# 2023-06-29_LVMi_Thermistors.net
KiCad netlist of a schematic drawn in EAGLE
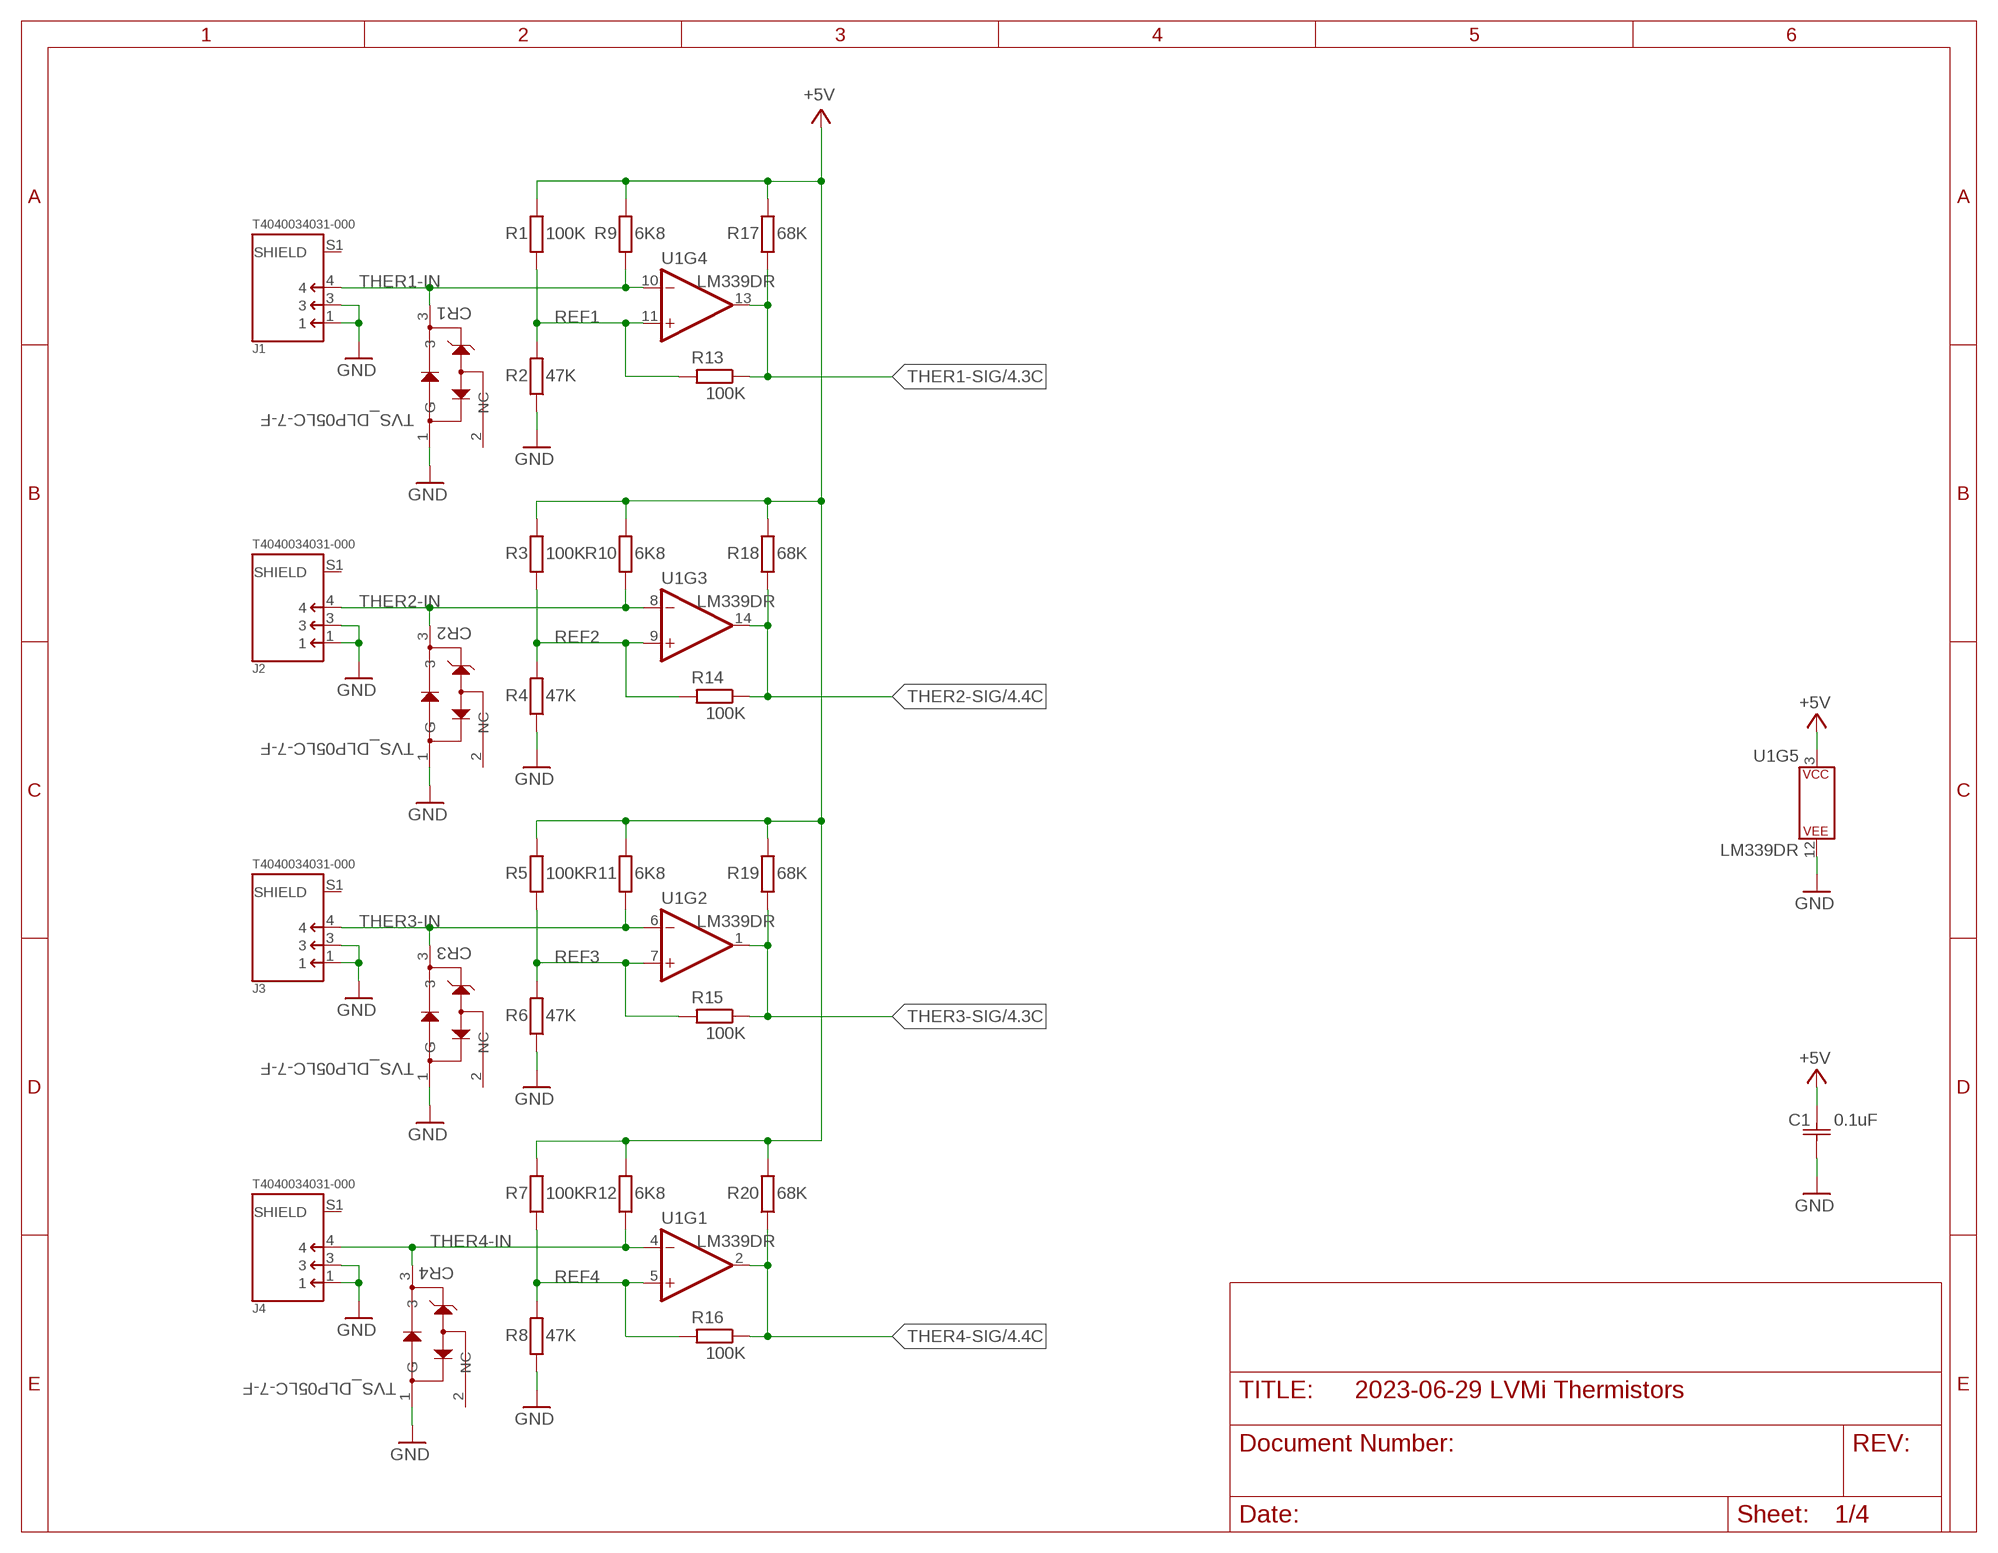
[diagram p0: schematic, sheet 1]
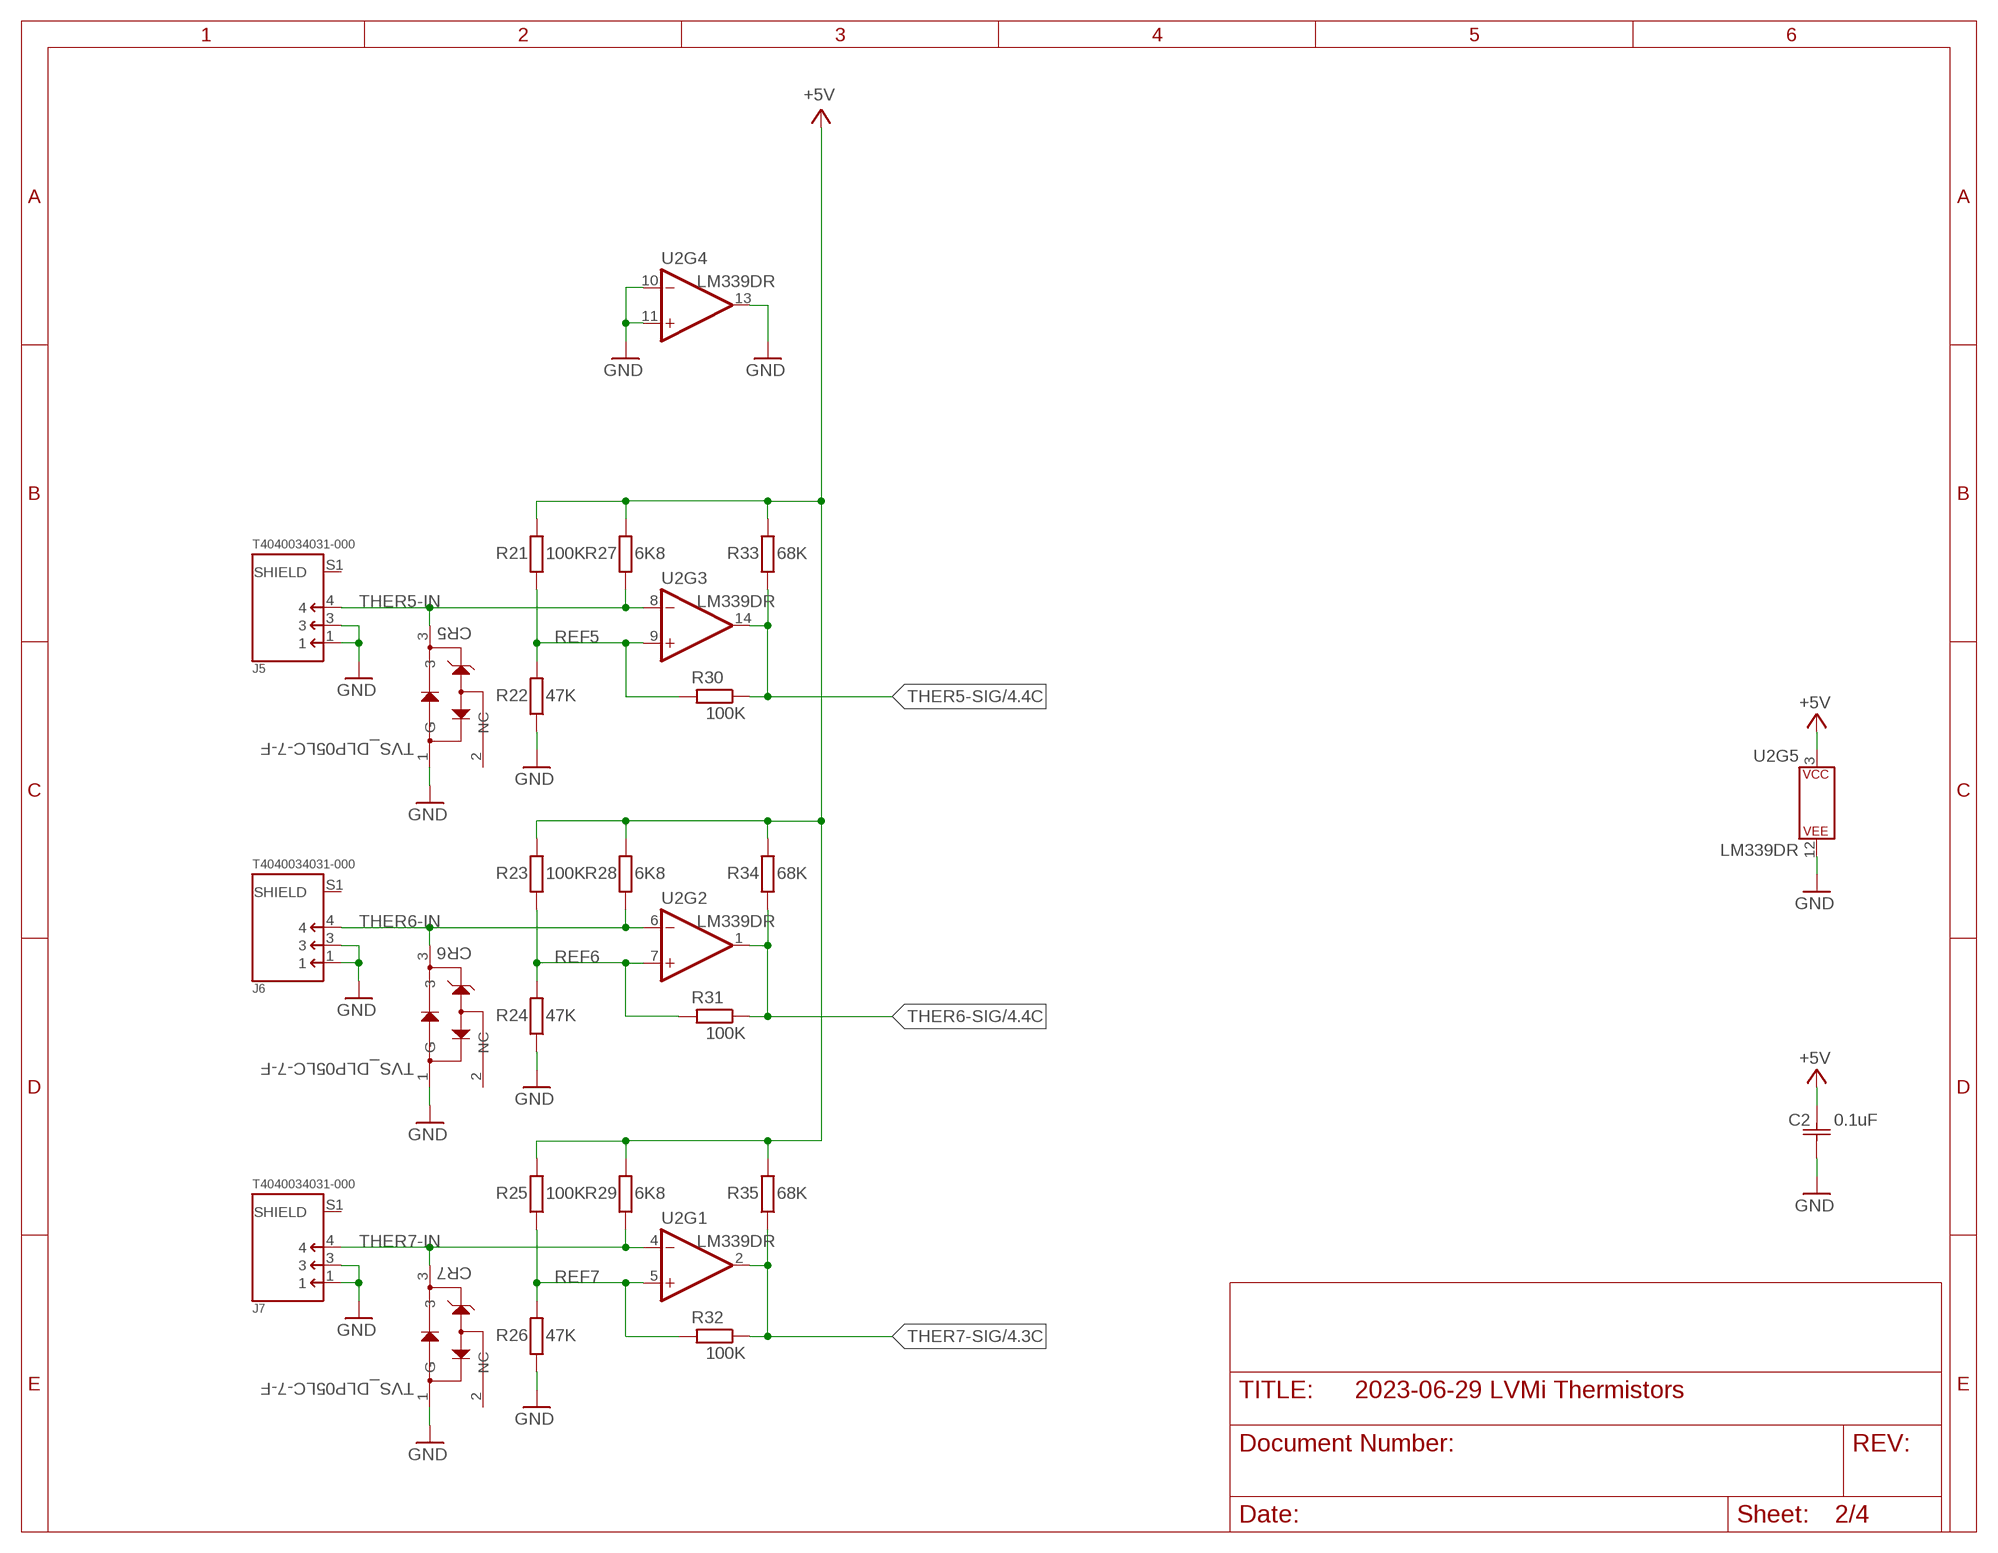
[diagram p1: schematic, sheet 2]
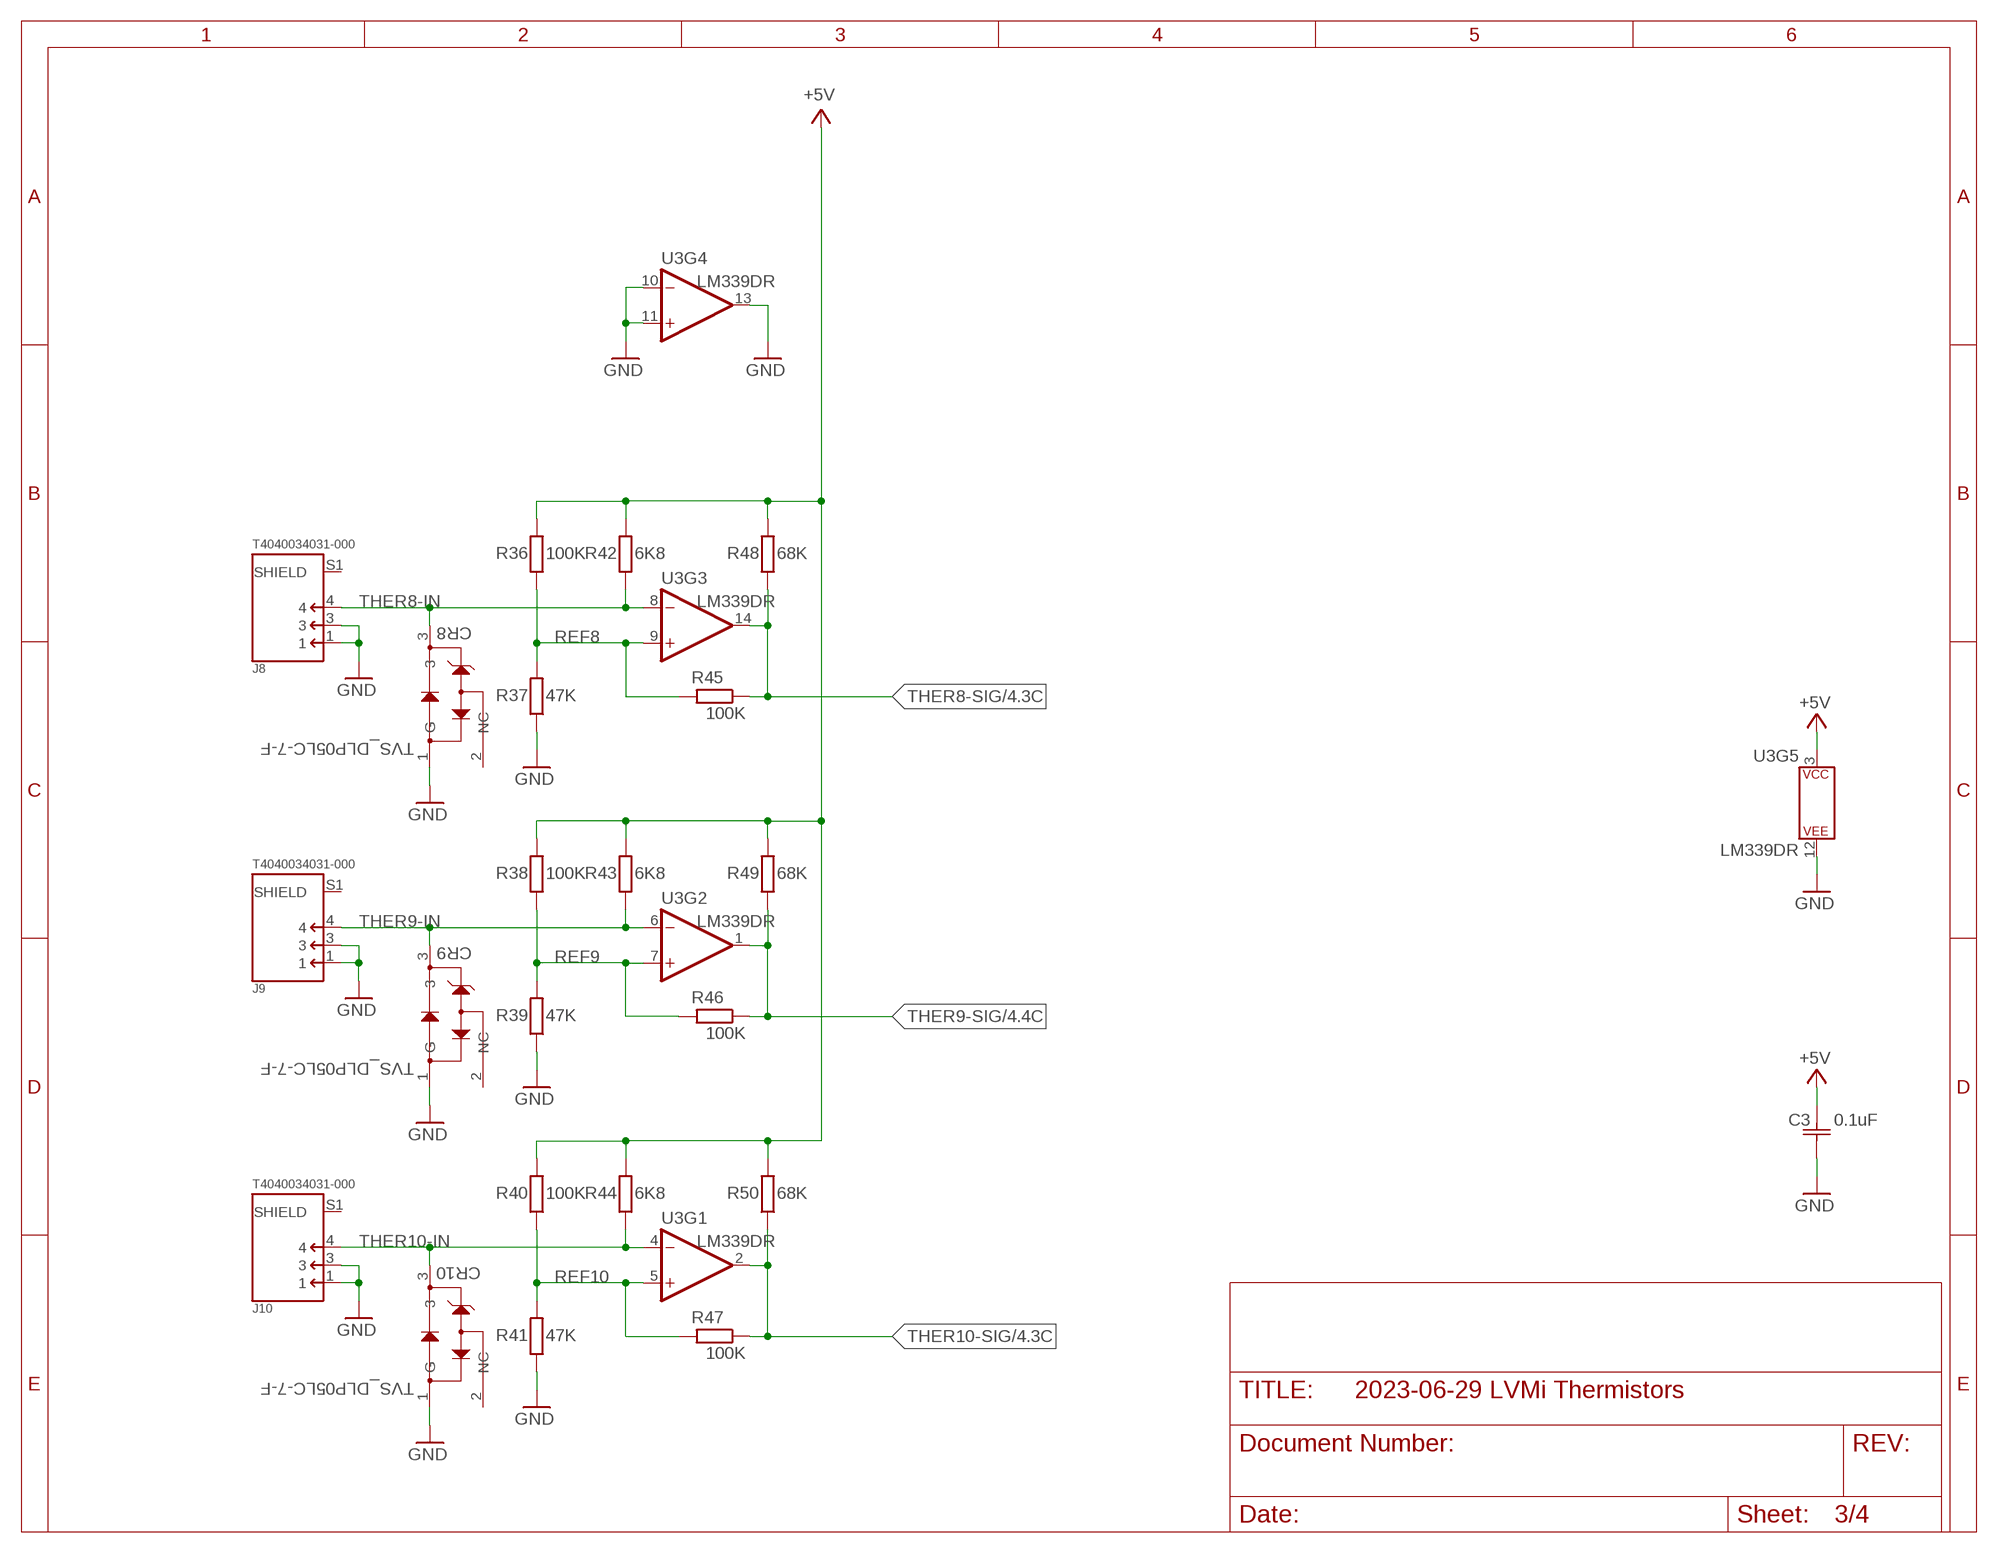
[diagram p2: schematic, sheet 3]
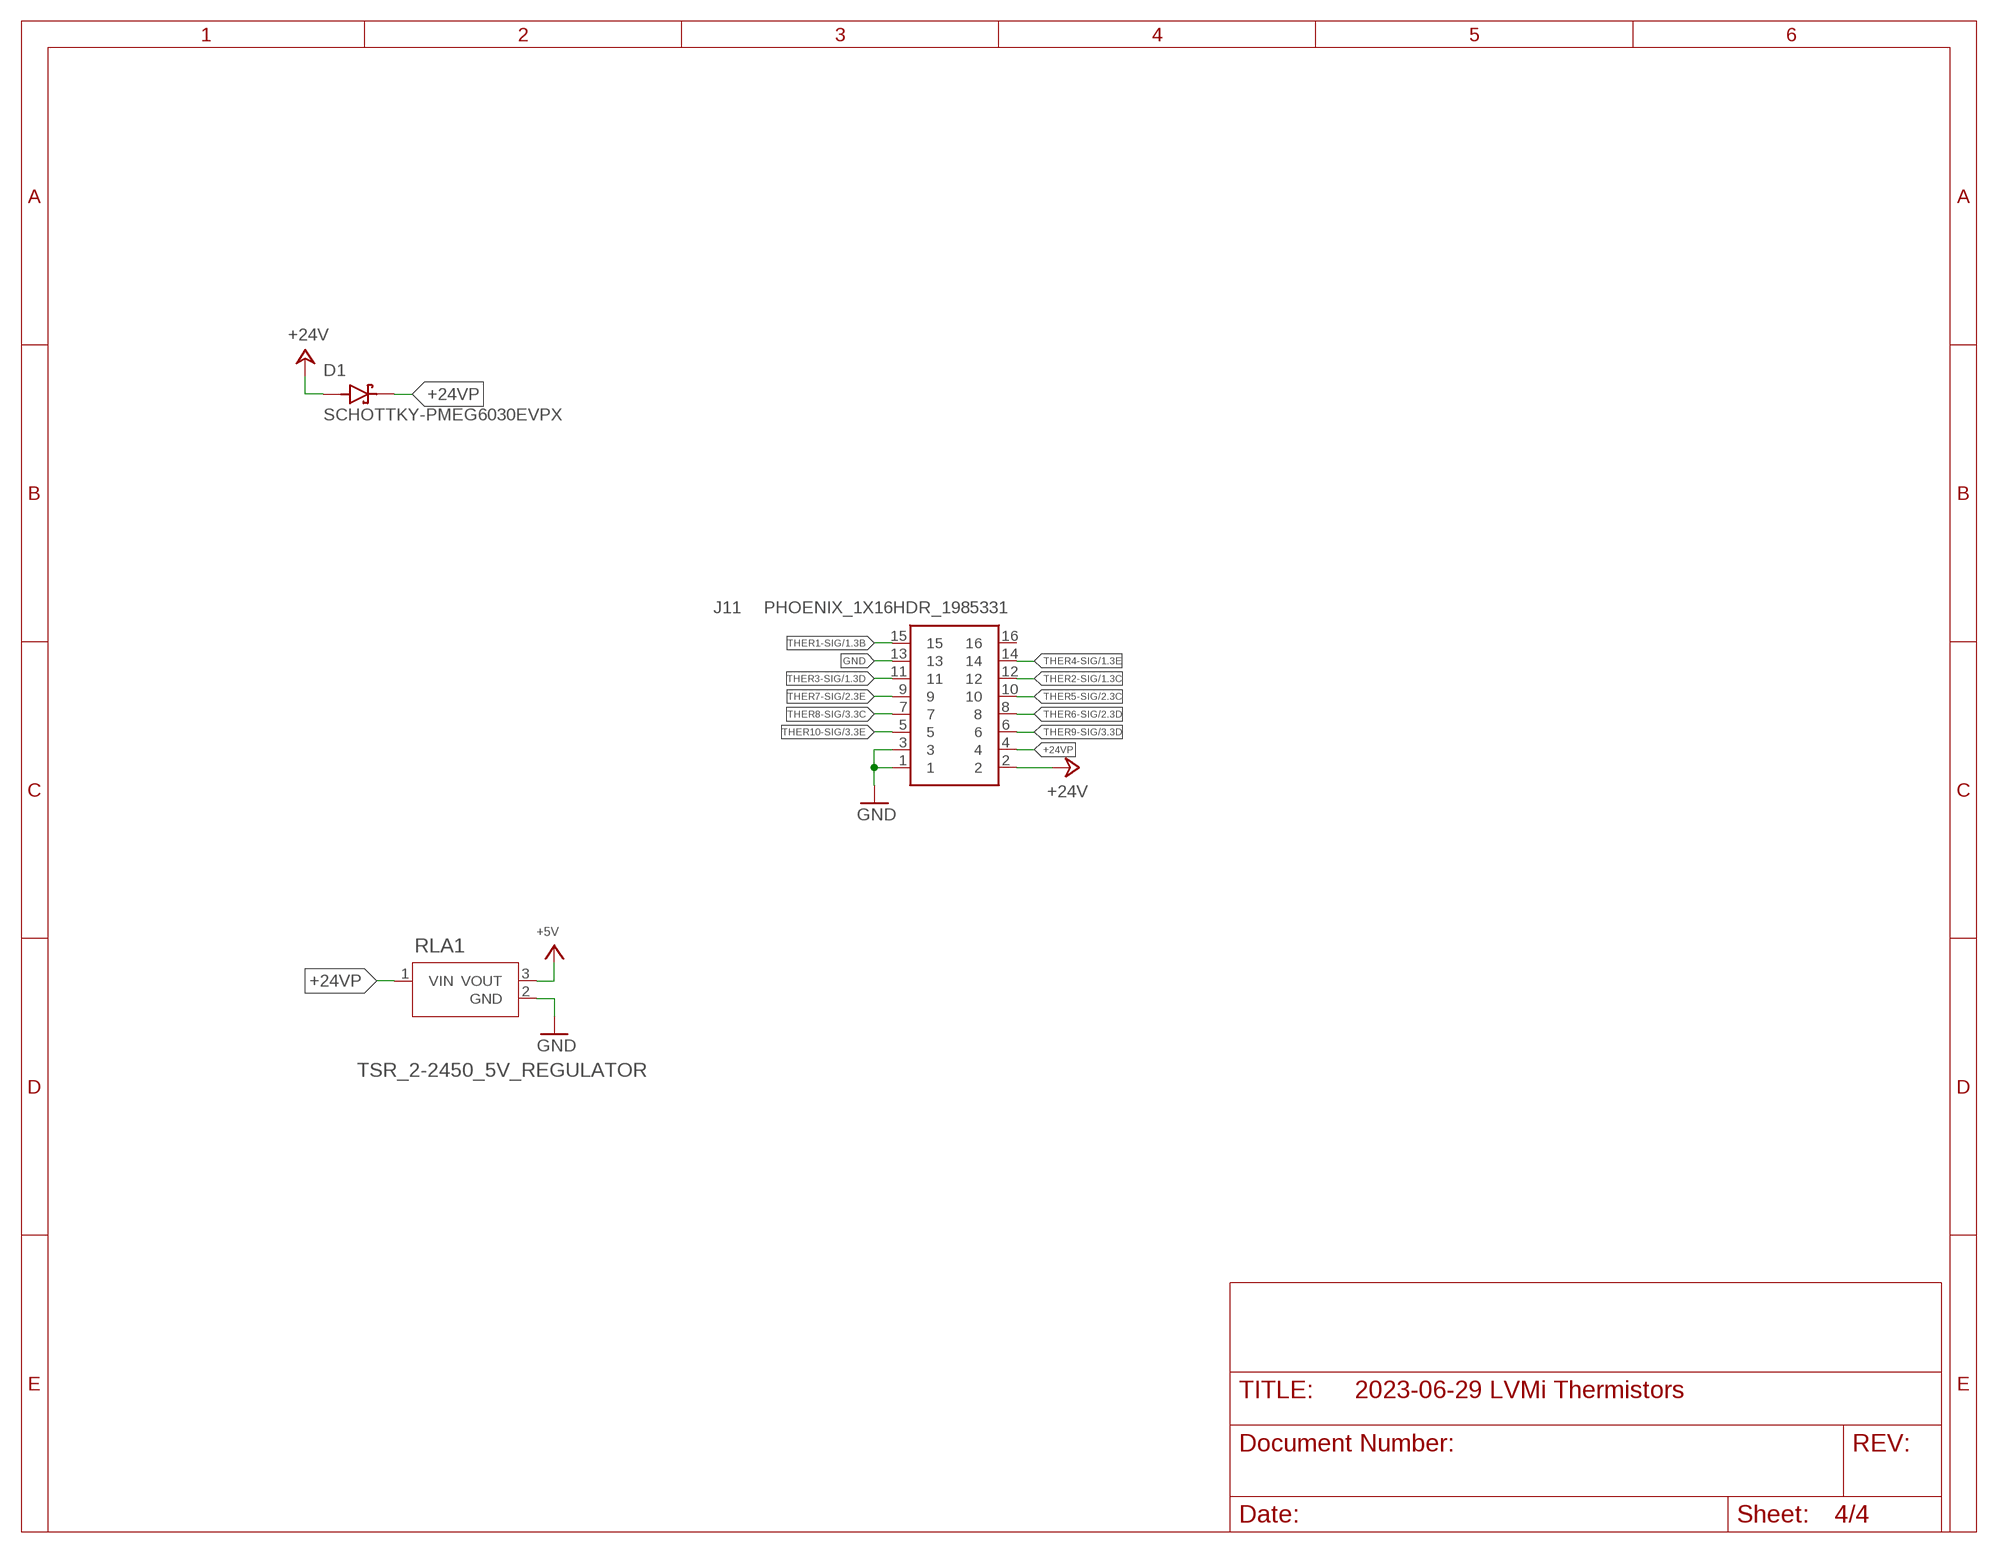
[diagram p3: schematic, sheet 4]

(export (version "E")
  (design (tool "Eeschema 10.0.6"))
  (components
    (comp (ref "D1")
      (value "SCHOTTKY-PMEG6030EVPX")
      (footprint "eagle-import:DIO_PMEG6030EVPX")
      (fields
        (field (name "DIGI-KEY_PART_NUMBER") "1727-1349-1-ND")
        (field (name "MF") "Nexperia USA")
        (field (name "MP") "PMEG6030EVPX")
      )
      (libsource (lib "eagle-import") (part "SCHOTTKY-PMEG6030EVPX"))
    )
    (comp (ref "J11")
      (value "PHOENIX_1X16HDR_1985331")
      (footprint "eagle-import:1985331")
      (fields
        (field (name "MANUFACTURER_PART_NUMBER") "1985331")
        (field (name "MOUSER_PART_NUMBER") "651-1985331")
      )
      (libsource (lib "eagle-import") (part "PHOENIX_1X16HDR_1985331"))
    )
    (comp (ref "RLA1")
      (value "TSR_2-2450_5V_REGULATOR")
      (footprint "eagle-import:TSR2-SINGLE_TRP")
      (fields
        (field (name "MANUFACTURER_PART_NUMBER") "TSR 2-2450")
        (field (name "COPYRIGHT") "Copyright (C) 2022 Ultra Librarian. All rights reserved.")
      )
      (libsource (lib "eagle-import") (part "TSR_2-2450_5V_REGULATOR"))
    )
    (comp (ref "C2")
      (value "0.1uF")
      (footprint "eagle-import:K104K15X7RF5TL2_VIS")
      (fields
        (field (name "MANUFACTURER_PART_NUMBER") "K104K15X7RF5TL2")
        (field (name "COPYRIGHT") "Copyright (C) 2023 Ultra Librarian. All rights reserved.")
      )
      (libsource (lib "eagle-import") (part "CAPTHRUHOLE"))
    )
    (comp (ref "CR5")
      (value "TVS_DLP05LC-7-F")
      (footprint "eagle-import:SOT23_DLP05LC_DIO")
      (fields
        (field (name "MANUFACTURER_PART_NUMBER") "DLP05LC-7-F")
        (field (name "COPYRIGHT") "Copyright (C) 2023 Ultra Librarian. All rights reserved.")
      )
      (libsource (lib "eagle-import") (part "TVS_DLP05LC-7-F"))
    )
    (comp (ref "CR6")
      (value "TVS_DLP05LC-7-F")
      (footprint "eagle-import:SOT23_DLP05LC_DIO")
      (fields
        (field (name "MANUFACTURER_PART_NUMBER") "DLP05LC-7-F")
        (field (name "COPYRIGHT") "Copyright (C) 2023 Ultra Librarian. All rights reserved.")
      )
      (libsource (lib "eagle-import") (part "TVS_DLP05LC-7-F"))
    )
    (comp (ref "CR7")
      (value "TVS_DLP05LC-7-F")
      (footprint "eagle-import:SOT23_DLP05LC_DIO")
      (fields
        (field (name "MANUFACTURER_PART_NUMBER") "DLP05LC-7-F")
        (field (name "COPYRIGHT") "Copyright (C) 2023 Ultra Librarian. All rights reserved.")
      )
      (libsource (lib "eagle-import") (part "TVS_DLP05LC-7-F"))
    )
    (comp (ref "J5")
      (value "T4040034031-000")
      (footprint "eagle-import:TE_T4040034031-000")
      (fields (field (name "MANUFACTURER") "TE "))
      (libsource (lib "eagle-import") (part "T4040034031-000"))
    )
    (comp (ref "J6")
      (value "T4040034031-000")
      (footprint "eagle-import:TE_T4040034031-000")
      (fields (field (name "MANUFACTURER") "TE "))
      (libsource (lib "eagle-import") (part "T4040034031-000"))
    )
    (comp (ref "J7")
      (value "T4040034031-000")
      (footprint "eagle-import:TE_T4040034031-000")
      (fields (field (name "MANUFACTURER") "TE "))
      (libsource (lib "eagle-import") (part "T4040034031-000"))
    )
    (comp (ref "R21")
      (value "100K")
      (footprint "eagle-import:0207_10")
      (libsource (lib "eagle-import") (part "R-EU_0207/10"))
    )
    (comp (ref "R22")
      (value "47K")
      (footprint "eagle-import:0207_10")
      (libsource (lib "eagle-import") (part "R-EU_0207/10"))
    )
    (comp (ref "R23")
      (value "100K")
      (footprint "eagle-import:0207_10")
      (libsource (lib "eagle-import") (part "R-EU_0207/10"))
    )
    (comp (ref "R24")
      (value "47K")
      (footprint "eagle-import:0207_10")
      (libsource (lib "eagle-import") (part "R-EU_0207/10"))
    )
    (comp (ref "R25")
      (value "100K")
      (footprint "eagle-import:0207_10")
      (libsource (lib "eagle-import") (part "R-EU_0207/10"))
    )
    (comp (ref "R26")
      (value "47K")
      (footprint "eagle-import:0207_10")
      (libsource (lib "eagle-import") (part "R-EU_0207/10"))
    )
    (comp (ref "R27")
      (value "6K8")
      (footprint "eagle-import:0207_10")
      (libsource (lib "eagle-import") (part "R-EU_0207/10"))
    )
    (comp (ref "R28")
      (value "6K8")
      (footprint "eagle-import:0207_10")
      (libsource (lib "eagle-import") (part "R-EU_0207/10"))
    )
    (comp (ref "R29")
      (value "6K8")
      (footprint "eagle-import:0207_10")
      (libsource (lib "eagle-import") (part "R-EU_0207/10"))
    )
    (comp (ref "R30")
      (value "100K")
      (footprint "eagle-import:0207_10")
      (libsource (lib "eagle-import") (part "R-EU_0207/10"))
    )
    (comp (ref "R31")
      (value "100K")
      (footprint "eagle-import:0207_10")
      (libsource (lib "eagle-import") (part "R-EU_0207/10"))
    )
    (comp (ref "R32")
      (value "100K")
      (footprint "eagle-import:0207_10")
      (libsource (lib "eagle-import") (part "R-EU_0207/10"))
    )
    (comp (ref "R33")
      (value "68K")
      (footprint "eagle-import:0207_10")
      (libsource (lib "eagle-import") (part "R-EU_0207/10"))
    )
    (comp (ref "R34")
      (value "68K")
      (footprint "eagle-import:0207_10")
      (libsource (lib "eagle-import") (part "R-EU_0207/10"))
    )
    (comp (ref "R35")
      (value "68K")
      (footprint "eagle-import:0207_10")
      (libsource (lib "eagle-import") (part "R-EU_0207/10"))
    )
    (comp (ref "U2")
      (value "LM339DR")
      (footprint "eagle-import:SOIC127P599X175-14")
      (libsource (lib "eagle-import") (part "LM339SOIC-14"))
    )
    (comp (ref "C3")
      (value "0.1uF")
      (footprint "eagle-import:K104K15X7RF5TL2_VIS")
      (fields
        (field (name "MANUFACTURER_PART_NUMBER") "K104K15X7RF5TL2")
        (field (name "COPYRIGHT") "Copyright (C) 2023 Ultra Librarian. All rights reserved.")
      )
      (libsource (lib "eagle-import") (part "CAPTHRUHOLE"))
    )
    (comp (ref "CR8")
      (value "TVS_DLP05LC-7-F")
      (footprint "eagle-import:SOT23_DLP05LC_DIO")
      (fields
        (field (name "MANUFACTURER_PART_NUMBER") "DLP05LC-7-F")
        (field (name "COPYRIGHT") "Copyright (C) 2023 Ultra Librarian. All rights reserved.")
      )
      (libsource (lib "eagle-import") (part "TVS_DLP05LC-7-F"))
    )
    (comp (ref "CR9")
      (value "TVS_DLP05LC-7-F")
      (footprint "eagle-import:SOT23_DLP05LC_DIO")
      (fields
        (field (name "MANUFACTURER_PART_NUMBER") "DLP05LC-7-F")
        (field (name "COPYRIGHT") "Copyright (C) 2023 Ultra Librarian. All rights reserved.")
      )
      (libsource (lib "eagle-import") (part "TVS_DLP05LC-7-F"))
    )
    (comp (ref "CR10")
      (value "TVS_DLP05LC-7-F")
      (footprint "eagle-import:SOT23_DLP05LC_DIO")
      (fields
        (field (name "MANUFACTURER_PART_NUMBER") "DLP05LC-7-F")
        (field (name "COPYRIGHT") "Copyright (C) 2023 Ultra Librarian. All rights reserved.")
      )
      (libsource (lib "eagle-import") (part "TVS_DLP05LC-7-F"))
    )
    (comp (ref "J8")
      (value "T4040034031-000")
      (footprint "eagle-import:TE_T4040034031-000")
      (fields (field (name "MANUFACTURER") "TE "))
      (libsource (lib "eagle-import") (part "T4040034031-000"))
    )
    (comp (ref "J9")
      (value "T4040034031-000")
      (footprint "eagle-import:TE_T4040034031-000")
      (fields (field (name "MANUFACTURER") "TE "))
      (libsource (lib "eagle-import") (part "T4040034031-000"))
    )
    (comp (ref "J10")
      (value "T4040034031-000")
      (footprint "eagle-import:TE_T4040034031-000")
      (fields (field (name "MANUFACTURER") "TE "))
      (libsource (lib "eagle-import") (part "T4040034031-000"))
    )
    (comp (ref "R36")
      (value "100K")
      (footprint "eagle-import:0207_10")
      (libsource (lib "eagle-import") (part "R-EU_0207/10"))
    )
    (comp (ref "R37")
      (value "47K")
      (footprint "eagle-import:0207_10")
      (libsource (lib "eagle-import") (part "R-EU_0207/10"))
    )
    (comp (ref "R38")
      (value "100K")
      (footprint "eagle-import:0207_10")
      (libsource (lib "eagle-import") (part "R-EU_0207/10"))
    )
    (comp (ref "R39")
      (value "47K")
      (footprint "eagle-import:0207_10")
      (libsource (lib "eagle-import") (part "R-EU_0207/10"))
    )
    (comp (ref "R40")
      (value "100K")
      (footprint "eagle-import:0207_10")
      (libsource (lib "eagle-import") (part "R-EU_0207/10"))
    )
    (comp (ref "R41")
      (value "47K")
      (footprint "eagle-import:0207_10")
      (libsource (lib "eagle-import") (part "R-EU_0207/10"))
    )
    (comp (ref "R42")
      (value "6K8")
      (footprint "eagle-import:0207_10")
      (libsource (lib "eagle-import") (part "R-EU_0207/10"))
    )
    (comp (ref "R43")
      (value "6K8")
      (footprint "eagle-import:0207_10")
      (libsource (lib "eagle-import") (part "R-EU_0207/10"))
    )
    (comp (ref "R44")
      (value "6K8")
      (footprint "eagle-import:0207_10")
      (libsource (lib "eagle-import") (part "R-EU_0207/10"))
    )
    (comp (ref "R45")
      (value "100K")
      (footprint "eagle-import:0207_10")
      (libsource (lib "eagle-import") (part "R-EU_0207/10"))
    )
    (comp (ref "R46")
      (value "100K")
      (footprint "eagle-import:0207_10")
      (libsource (lib "eagle-import") (part "R-EU_0207/10"))
    )
    (comp (ref "R47")
      (value "100K")
      (footprint "eagle-import:0207_10")
      (libsource (lib "eagle-import") (part "R-EU_0207/10"))
    )
    (comp (ref "R48")
      (value "68K")
      (footprint "eagle-import:0207_10")
      (libsource (lib "eagle-import") (part "R-EU_0207/10"))
    )
    (comp (ref "R49")
      (value "68K")
      (footprint "eagle-import:0207_10")
      (libsource (lib "eagle-import") (part "R-EU_0207/10"))
    )
    (comp (ref "R50")
      (value "68K")
      (footprint "eagle-import:0207_10")
      (libsource (lib "eagle-import") (part "R-EU_0207/10"))
    )
    (comp (ref "U3")
      (value "LM339DR")
      (footprint "eagle-import:SOIC127P599X175-14")
      (libsource (lib "eagle-import") (part "LM339SOIC-14"))
    )
    (comp (ref "C1")
      (value "0.1uF")
      (footprint "eagle-import:K104K15X7RF5TL2_VIS")
      (fields
        (field (name "MANUFACTURER_PART_NUMBER") "K104K15X7RF5TL2")
        (field (name "COPYRIGHT") "Copyright (C) 2023 Ultra Librarian. All rights reserved.")
      )
      (libsource (lib "eagle-import") (part "CAPTHRUHOLE"))
    )
    (comp (ref "CR1")
      (value "TVS_DLP05LC-7-F")
      (footprint "eagle-import:SOT23_DLP05LC_DIO")
      (fields
        (field (name "MANUFACTURER_PART_NUMBER") "DLP05LC-7-F")
        (field (name "COPYRIGHT") "Copyright (C) 2023 Ultra Librarian. All rights reserved.")
      )
      (libsource (lib "eagle-import") (part "TVS_DLP05LC-7-F"))
    )
    (comp (ref "CR2")
      (value "TVS_DLP05LC-7-F")
      (footprint "eagle-import:SOT23_DLP05LC_DIO")
      (fields
        (field (name "MANUFACTURER_PART_NUMBER") "DLP05LC-7-F")
        (field (name "COPYRIGHT") "Copyright (C) 2023 Ultra Librarian. All rights reserved.")
      )
      (libsource (lib "eagle-import") (part "TVS_DLP05LC-7-F"))
    )
    (comp (ref "CR3")
      (value "TVS_DLP05LC-7-F")
      (footprint "eagle-import:SOT23_DLP05LC_DIO")
      (fields
        (field (name "MANUFACTURER_PART_NUMBER") "DLP05LC-7-F")
        (field (name "COPYRIGHT") "Copyright (C) 2023 Ultra Librarian. All rights reserved.")
      )
      (libsource (lib "eagle-import") (part "TVS_DLP05LC-7-F"))
    )
    (comp (ref "CR4")
      (value "TVS_DLP05LC-7-F")
      (footprint "eagle-import:SOT23_DLP05LC_DIO")
      (fields
        (field (name "MANUFACTURER_PART_NUMBER") "DLP05LC-7-F")
        (field (name "COPYRIGHT") "Copyright (C) 2023 Ultra Librarian. All rights reserved.")
      )
      (libsource (lib "eagle-import") (part "TVS_DLP05LC-7-F"))
    )
    (comp (ref "J1")
      (value "T4040034031-000")
      (footprint "eagle-import:TE_T4040034031-000")
      (fields (field (name "MANUFACTURER") "TE "))
      (libsource (lib "eagle-import") (part "T4040034031-000"))
    )
    (comp (ref "J2")
      (value "T4040034031-000")
      (footprint "eagle-import:TE_T4040034031-000")
      (fields (field (name "MANUFACTURER") "TE "))
      (libsource (lib "eagle-import") (part "T4040034031-000"))
    )
    (comp (ref "J3")
      (value "T4040034031-000")
      (footprint "eagle-import:TE_T4040034031-000")
      (fields (field (name "MANUFACTURER") "TE "))
      (libsource (lib "eagle-import") (part "T4040034031-000"))
    )
    (comp (ref "J4")
      (value "T4040034031-000")
      (footprint "eagle-import:TE_T4040034031-000")
      (fields (field (name "MANUFACTURER") "TE "))
      (libsource (lib "eagle-import") (part "T4040034031-000"))
    )
    (comp (ref "R1")
      (value "100K")
      (footprint "eagle-import:0207_10")
      (libsource (lib "eagle-import") (part "R-EU_0207/10"))
    )
    (comp (ref "R2")
      (value "47K")
      (footprint "eagle-import:0207_10")
      (libsource (lib "eagle-import") (part "R-EU_0207/10"))
    )
    (comp (ref "R3")
      (value "100K")
      (footprint "eagle-import:0207_10")
      (libsource (lib "eagle-import") (part "R-EU_0207/10"))
    )
    (comp (ref "R4")
      (value "47K")
      (footprint "eagle-import:0207_10")
      (libsource (lib "eagle-import") (part "R-EU_0207/10"))
    )
    (comp (ref "R5")
      (value "100K")
      (footprint "eagle-import:0207_10")
      (libsource (lib "eagle-import") (part "R-EU_0207/10"))
    )
    (comp (ref "R6")
      (value "47K")
      (footprint "eagle-import:0207_10")
      (libsource (lib "eagle-import") (part "R-EU_0207/10"))
    )
    (comp (ref "R7")
      (value "100K")
      (footprint "eagle-import:0207_10")
      (libsource (lib "eagle-import") (part "R-EU_0207/10"))
    )
    (comp (ref "R8")
      (value "47K")
      (footprint "eagle-import:0207_10")
      (libsource (lib "eagle-import") (part "R-EU_0207/10"))
    )
    (comp (ref "R9")
      (value "6K8")
      (footprint "eagle-import:0207_10")
      (libsource (lib "eagle-import") (part "R-EU_0207/10"))
    )
    (comp (ref "R10")
      (value "6K8")
      (footprint "eagle-import:0207_10")
      (libsource (lib "eagle-import") (part "R-EU_0207/10"))
    )
    (comp (ref "R11")
      (value "6K8")
      (footprint "eagle-import:0207_10")
      (libsource (lib "eagle-import") (part "R-EU_0207/10"))
    )
    (comp (ref "R12")
      (value "6K8")
      (footprint "eagle-import:0207_10")
      (libsource (lib "eagle-import") (part "R-EU_0207/10"))
    )
    (comp (ref "R13")
      (value "100K")
      (footprint "eagle-import:0207_10")
      (libsource (lib "eagle-import") (part "R-EU_0207/10"))
    )
    (comp (ref "R14")
      (value "100K")
      (footprint "eagle-import:0207_10")
      (libsource (lib "eagle-import") (part "R-EU_0207/10"))
    )
    (comp (ref "R15")
      (value "100K")
      (footprint "eagle-import:0207_10")
      (libsource (lib "eagle-import") (part "R-EU_0207/10"))
    )
    (comp (ref "R16")
      (value "100K")
      (footprint "eagle-import:0207_10")
      (libsource (lib "eagle-import") (part "R-EU_0207/10"))
    )
    (comp (ref "R17")
      (value "68K")
      (footprint "eagle-import:0207_10")
      (libsource (lib "eagle-import") (part "R-EU_0207/10"))
    )
    (comp (ref "R18")
      (value "68K")
      (footprint "eagle-import:0207_10")
      (libsource (lib "eagle-import") (part "R-EU_0207/10"))
    )
    (comp (ref "R19")
      (value "68K")
      (footprint "eagle-import:0207_10")
      (libsource (lib "eagle-import") (part "R-EU_0207/10"))
    )
    (comp (ref "R20")
      (value "68K")
      (footprint "eagle-import:0207_10")
      (libsource (lib "eagle-import") (part "R-EU_0207/10"))
    )
    (comp (ref "U1")
      (value "LM339DR")
      (footprint "eagle-import:SOIC127P599X175-14")
      (libsource (lib "eagle-import") (part "LM339SOIC-14"))
    )
  )
  (nets
    (net (code "1") (name "+5V") (class "Default")
      (node (ref "C1") (pin "2") (pinfunction "2_2") (pintype "passive"))
      (node (ref "C2") (pin "2") (pinfunction "2_2") (pintype "passive"))
      (node (ref "C3") (pin "2") (pinfunction "2_2") (pintype "passive"))
      (node (ref "R1") (pin "2") (pinfunction "2_2") (pintype "passive"))
      (node (ref "R10") (pin "2") (pinfunction "2_2") (pintype "passive"))
      (node (ref "R11") (pin "2") (pinfunction "2_2") (pintype "passive"))
      (node (ref "R12") (pin "2") (pinfunction "2_2") (pintype "passive"))
      (node (ref "R17") (pin "2") (pinfunction "2_2") (pintype "passive"))
      (node (ref "R18") (pin "2") (pinfunction "2_2") (pintype "passive"))
      (node (ref "R19") (pin "2") (pinfunction "2_2") (pintype "passive"))
      (node (ref "R20") (pin "2") (pinfunction "2_2") (pintype "passive"))
      (node (ref "R21") (pin "2") (pinfunction "2_2") (pintype "passive"))
      (node (ref "R23") (pin "2") (pinfunction "2_2") (pintype "passive"))
      (node (ref "R25") (pin "2") (pinfunction "2_2") (pintype "passive"))
      (node (ref "R27") (pin "2") (pinfunction "2_2") (pintype "passive"))
      (node (ref "R28") (pin "2") (pinfunction "2_2") (pintype "passive"))
      (node (ref "R29") (pin "2") (pinfunction "2_2") (pintype "passive"))
      (node (ref "R3") (pin "2") (pinfunction "2_2") (pintype "passive"))
      (node (ref "R33") (pin "2") (pinfunction "2_2") (pintype "passive"))
      (node (ref "R34") (pin "2") (pinfunction "2_2") (pintype "passive"))
      (node (ref "R35") (pin "2") (pinfunction "2_2") (pintype "passive"))
      (node (ref "R36") (pin "2") (pinfunction "2_2") (pintype "passive"))
      (node (ref "R38") (pin "2") (pinfunction "2_2") (pintype "passive"))
      (node (ref "R40") (pin "2") (pinfunction "2_2") (pintype "passive"))
      (node (ref "R42") (pin "2") (pinfunction "2_2") (pintype "passive"))
      (node (ref "R43") (pin "2") (pinfunction "2_2") (pintype "passive"))
      (node (ref "R44") (pin "2") (pinfunction "2_2") (pintype "passive"))
      (node (ref "R48") (pin "2") (pinfunction "2_2") (pintype "passive"))
      (node (ref "R49") (pin "2") (pinfunction "2_2") (pintype "passive"))
      (node (ref "R5") (pin "2") (pinfunction "2_2") (pintype "passive"))
      (node (ref "R50") (pin "2") (pinfunction "2_2") (pintype "passive"))
      (node (ref "R7") (pin "2") (pinfunction "2_2") (pintype "passive"))
      (node (ref "R9") (pin "2") (pinfunction "2_2") (pintype "passive"))
      (node (ref "RLA1") (pin "3") (pinfunction "VOUT_3") (pintype "passive"))
      (node (ref "U1") (pin "3") (pinfunction "P$V+_3") (pintype "bidirectional"))
      (node (ref "U2") (pin "3") (pinfunction "P$V+_3") (pintype "bidirectional"))
      (node (ref "U3") (pin "3") (pinfunction "P$V+_3") (pintype "bidirectional"))
    )
    (net (code "2") (name "+24V") (class "Default")
      (node (ref "D1") (pin "2") (pinfunction "A_2") (pintype "passive"))
      (node (ref "J11") (pin "2") (pinfunction "2_2") (pintype "bidirectional"))
    )
    (net (code "3") (name "+24VP") (class "Default")
      (node (ref "D1") (pin "1") (pinfunction "K_1") (pintype "passive"))
      (node (ref "J11") (pin "4") (pinfunction "4_4") (pintype "bidirectional"))
      (node (ref "RLA1") (pin "1") (pinfunction "VIN_1") (pintype "passive"))
    )
    (net (code "4") (name "GND") (class "Default")
      (node (ref "C1") (pin "1") (pinfunction "1_1") (pintype "passive"))
      (node (ref "C2") (pin "1") (pinfunction "1_1") (pintype "passive"))
      (node (ref "C3") (pin "1") (pinfunction "1_1") (pintype "passive"))
      (node (ref "CR1") (pin "1") (pinfunction "G_1") (pintype "passive"))
      (node (ref "CR10") (pin "1") (pinfunction "G_1") (pintype "passive"))
      (node (ref "CR2") (pin "1") (pinfunction "G_1") (pintype "passive"))
      (node (ref "CR3") (pin "1") (pinfunction "G_1") (pintype "passive"))
      (node (ref "CR4") (pin "1") (pinfunction "G_1") (pintype "passive"))
      (node (ref "CR5") (pin "1") (pinfunction "G_1") (pintype "passive"))
      (node (ref "CR6") (pin "1") (pinfunction "G_1") (pintype "passive"))
      (node (ref "CR7") (pin "1") (pinfunction "G_1") (pintype "passive"))
      (node (ref "CR8") (pin "1") (pinfunction "G_1") (pintype "passive"))
      (node (ref "CR9") (pin "1") (pinfunction "G_1") (pintype "passive"))
      (node (ref "J1") (pin "1") (pinfunction "1_1") (pintype "passive"))
      (node (ref "J1") (pin "3") (pinfunction "3_3") (pintype "passive"))
      (node (ref "J10") (pin "1") (pinfunction "1_1") (pintype "passive"))
      (node (ref "J10") (pin "3") (pinfunction "3_3") (pintype "passive"))
      (node (ref "J11") (pin "1") (pinfunction "1_1") (pintype "bidirectional"))
      (node (ref "J11") (pin "13") (pinfunction "13_13") (pintype "bidirectional"))
      (node (ref "J11") (pin "3") (pinfunction "3_3") (pintype "bidirectional"))
      (node (ref "J2") (pin "1") (pinfunction "1_1") (pintype "passive"))
      (node (ref "J2") (pin "3") (pinfunction "3_3") (pintype "passive"))
      (node (ref "J3") (pin "1") (pinfunction "1_1") (pintype "passive"))
      (node (ref "J3") (pin "3") (pinfunction "3_3") (pintype "passive"))
      (node (ref "J4") (pin "1") (pinfunction "1_1") (pintype "passive"))
      (node (ref "J4") (pin "3") (pinfunction "3_3") (pintype "passive"))
      (node (ref "J5") (pin "1") (pinfunction "1_1") (pintype "passive"))
      (node (ref "J5") (pin "3") (pinfunction "3_3") (pintype "passive"))
      (node (ref "J6") (pin "1") (pinfunction "1_1") (pintype "passive"))
      (node (ref "J6") (pin "3") (pinfunction "3_3") (pintype "passive"))
      (node (ref "J7") (pin "1") (pinfunction "1_1") (pintype "passive"))
      (node (ref "J7") (pin "3") (pinfunction "3_3") (pintype "passive"))
      (node (ref "J8") (pin "1") (pinfunction "1_1") (pintype "passive"))
      (node (ref "J8") (pin "3") (pinfunction "3_3") (pintype "passive"))
      (node (ref "J9") (pin "1") (pinfunction "1_1") (pintype "passive"))
      (node (ref "J9") (pin "3") (pinfunction "3_3") (pintype "passive"))
      (node (ref "R2") (pin "1") (pinfunction "1_1") (pintype "passive"))
      (node (ref "R22") (pin "1") (pinfunction "1_1") (pintype "passive"))
      (node (ref "R24") (pin "1") (pinfunction "1_1") (pintype "passive"))
      (node (ref "R26") (pin "1") (pinfunction "1_1") (pintype "passive"))
      (node (ref "R37") (pin "1") (pinfunction "1_1") (pintype "passive"))
      (node (ref "R39") (pin "1") (pinfunction "1_1") (pintype "passive"))
      (node (ref "R4") (pin "1") (pinfunction "1_1") (pintype "passive"))
      (node (ref "R41") (pin "1") (pinfunction "1_1") (pintype "passive"))
      (node (ref "R6") (pin "1") (pinfunction "1_1") (pintype "passive"))
      (node (ref "R8") (pin "1") (pinfunction "1_1") (pintype "passive"))
      (node (ref "RLA1") (pin "2") (pinfunction "GND_2") (pintype "passive"))
      (node (ref "U1") (pin "12") (pinfunction "P$V-_12") (pintype "bidirectional"))
      (node (ref "U2") (pin "10") (pinfunction "-IN_10") (pintype "input"))
      (node (ref "U2") (pin "11") (pinfunction "+IN_11") (pintype "input"))
      (node (ref "U2") (pin "12") (pinfunction "P$V-_12") (pintype "bidirectional"))
      (node (ref "U2") (pin "13") (pinfunction "OUT_13") (pintype "output"))
      (node (ref "U3") (pin "10") (pinfunction "-IN_10") (pintype "input"))
      (node (ref "U3") (pin "11") (pinfunction "+IN_11") (pintype "input"))
      (node (ref "U3") (pin "12") (pinfunction "P$V-_12") (pintype "bidirectional"))
      (node (ref "U3") (pin "13") (pinfunction "OUT_13") (pintype "output"))
    )
    (net (code "5") (name "REF1") (class "Default")
      (node (ref "R1") (pin "1") (pinfunction "1_1") (pintype "passive"))
      (node (ref "R13") (pin "2") (pinfunction "2_2") (pintype "passive"))
      (node (ref "R2") (pin "2") (pinfunction "2_2") (pintype "passive"))
      (node (ref "U1") (pin "11") (pinfunction "+IN_11") (pintype "input"))
    )
    (net (code "6") (name "REF2") (class "Default")
      (node (ref "R14") (pin "2") (pinfunction "2_2") (pintype "passive"))
      (node (ref "R3") (pin "1") (pinfunction "1_1") (pintype "passive"))
      (node (ref "R4") (pin "2") (pinfunction "2_2") (pintype "passive"))
      (node (ref "U1") (pin "9") (pinfunction "+IN_9") (pintype "input"))
    )
    (net (code "7") (name "REF3") (class "Default")
      (node (ref "R15") (pin "2") (pinfunction "2_2") (pintype "passive"))
      (node (ref "R5") (pin "1") (pinfunction "1_1") (pintype "passive"))
      (node (ref "R6") (pin "2") (pinfunction "2_2") (pintype "passive"))
      (node (ref "U1") (pin "7") (pinfunction "+IN_7") (pintype "input"))
    )
    (net (code "8") (name "REF4") (class "Default")
      (node (ref "R16") (pin "2") (pinfunction "2_2") (pintype "passive"))
      (node (ref "R7") (pin "1") (pinfunction "1_1") (pintype "passive"))
      (node (ref "R8") (pin "2") (pinfunction "2_2") (pintype "passive"))
      (node (ref "U1") (pin "5") (pinfunction "+IN_5") (pintype "input"))
    )
    (net (code "9") (name "REF5") (class "Default")
      (node (ref "R21") (pin "1") (pinfunction "1_1") (pintype "passive"))
      (node (ref "R22") (pin "2") (pinfunction "2_2") (pintype "passive"))
      (node (ref "R30") (pin "2") (pinfunction "2_2") (pintype "passive"))
      (node (ref "U2") (pin "9") (pinfunction "+IN_9") (pintype "input"))
    )
    (net (code "10") (name "REF6") (class "Default")
      (node (ref "R23") (pin "1") (pinfunction "1_1") (pintype "passive"))
      (node (ref "R24") (pin "2") (pinfunction "2_2") (pintype "passive"))
      (node (ref "R31") (pin "2") (pinfunction "2_2") (pintype "passive"))
      (node (ref "U2") (pin "7") (pinfunction "+IN_7") (pintype "input"))
    )
    (net (code "11") (name "REF7") (class "Default")
      (node (ref "R25") (pin "1") (pinfunction "1_1") (pintype "passive"))
      (node (ref "R26") (pin "2") (pinfunction "2_2") (pintype "passive"))
      (node (ref "R32") (pin "2") (pinfunction "2_2") (pintype "passive"))
      (node (ref "U2") (pin "5") (pinfunction "+IN_5") (pintype "input"))
    )
    (net (code "12") (name "REF8") (class "Default")
      (node (ref "R36") (pin "1") (pinfunction "1_1") (pintype "passive"))
      (node (ref "R37") (pin "2") (pinfunction "2_2") (pintype "passive"))
      (node (ref "R45") (pin "2") (pinfunction "2_2") (pintype "passive"))
      (node (ref "U3") (pin "9") (pinfunction "+IN_9") (pintype "input"))
    )
    (net (code "13") (name "REF9") (class "Default")
      (node (ref "R38") (pin "1") (pinfunction "1_1") (pintype "passive"))
      (node (ref "R39") (pin "2") (pinfunction "2_2") (pintype "passive"))
      (node (ref "R46") (pin "2") (pinfunction "2_2") (pintype "passive"))
      (node (ref "U3") (pin "7") (pinfunction "+IN_7") (pintype "input"))
    )
    (net (code "14") (name "REF10") (class "Default")
      (node (ref "R40") (pin "1") (pinfunction "1_1") (pintype "passive"))
      (node (ref "R41") (pin "2") (pinfunction "2_2") (pintype "passive"))
      (node (ref "R47") (pin "2") (pinfunction "2_2") (pintype "passive"))
      (node (ref "U3") (pin "5") (pinfunction "+IN_5") (pintype "input"))
    )
    (net (code "15") (name "THER1-IN") (class "Default")
      (node (ref "CR1") (pin "3") (pinfunction "3_3") (pintype "passive"))
      (node (ref "J1") (pin "4") (pinfunction "4_4") (pintype "passive"))
      (node (ref "R9") (pin "1") (pinfunction "1_1") (pintype "passive"))
      (node (ref "U1") (pin "10") (pinfunction "-IN_10") (pintype "input"))
    )
    (net (code "16") (name "THER1-SIG") (class "Default")
      (node (ref "J11") (pin "15") (pinfunction "15_15") (pintype "bidirectional"))
      (node (ref "R13") (pin "1") (pinfunction "1_1") (pintype "passive"))
      (node (ref "R17") (pin "1") (pinfunction "1_1") (pintype "passive"))
      (node (ref "U1") (pin "13") (pinfunction "OUT_13") (pintype "output"))
    )
    (net (code "17") (name "THER2-IN") (class "Default")
      (node (ref "CR2") (pin "3") (pinfunction "3_3") (pintype "passive"))
      (node (ref "J2") (pin "4") (pinfunction "4_4") (pintype "passive"))
      (node (ref "R10") (pin "1") (pinfunction "1_1") (pintype "passive"))
      (node (ref "U1") (pin "8") (pinfunction "-IN_8") (pintype "input"))
    )
    (net (code "18") (name "THER2-SIG") (class "Default")
      (node (ref "J11") (pin "12") (pinfunction "12_12") (pintype "bidirectional"))
      (node (ref "R14") (pin "1") (pinfunction "1_1") (pintype "passive"))
      (node (ref "R18") (pin "1") (pinfunction "1_1") (pintype "passive"))
      (node (ref "U1") (pin "14") (pinfunction "OUT_14") (pintype "output"))
    )
    (net (code "19") (name "THER3-IN") (class "Default")
      (node (ref "CR3") (pin "3") (pinfunction "3_3") (pintype "passive"))
      (node (ref "J3") (pin "4") (pinfunction "4_4") (pintype "passive"))
      (node (ref "R11") (pin "1") (pinfunction "1_1") (pintype "passive"))
      (node (ref "U1") (pin "6") (pinfunction "-IN_6") (pintype "input"))
    )
    (net (code "20") (name "THER3-SIG") (class "Default")
      (node (ref "J11") (pin "11") (pinfunction "11_11") (pintype "bidirectional"))
      (node (ref "R15") (pin "1") (pinfunction "1_1") (pintype "passive"))
      (node (ref "R19") (pin "1") (pinfunction "1_1") (pintype "passive"))
      (node (ref "U1") (pin "1") (pinfunction "OUT_1") (pintype "output"))
    )
    (net (code "21") (name "THER4-IN") (class "Default")
      (node (ref "CR4") (pin "3") (pinfunction "3_3") (pintype "passive"))
      (node (ref "J4") (pin "4") (pinfunction "4_4") (pintype "passive"))
      (node (ref "R12") (pin "1") (pinfunction "1_1") (pintype "passive"))
      (node (ref "U1") (pin "4") (pinfunction "-IN_4") (pintype "input"))
    )
    (net (code "22") (name "THER4-SIG") (class "Default")
      (node (ref "J11") (pin "14") (pinfunction "14_14") (pintype "bidirectional"))
      (node (ref "R16") (pin "1") (pinfunction "1_1") (pintype "passive"))
      (node (ref "R20") (pin "1") (pinfunction "1_1") (pintype "passive"))
      (node (ref "U1") (pin "2") (pinfunction "OUT_2") (pintype "output"))
    )
    (net (code "23") (name "THER5-IN") (class "Default")
      (node (ref "CR5") (pin "3") (pinfunction "3_3") (pintype "passive"))
      (node (ref "J5") (pin "4") (pinfunction "4_4") (pintype "passive"))
      (node (ref "R27") (pin "1") (pinfunction "1_1") (pintype "passive"))
      (node (ref "U2") (pin "8") (pinfunction "-IN_8") (pintype "input"))
    )
    (net (code "24") (name "THER5-SIG") (class "Default")
      (node (ref "J11") (pin "10") (pinfunction "10_10") (pintype "bidirectional"))
      (node (ref "R30") (pin "1") (pinfunction "1_1") (pintype "passive"))
      (node (ref "R33") (pin "1") (pinfunction "1_1") (pintype "passive"))
      (node (ref "U2") (pin "14") (pinfunction "OUT_14") (pintype "output"))
    )
    (net (code "25") (name "THER6-IN") (class "Default")
      (node (ref "CR6") (pin "3") (pinfunction "3_3") (pintype "passive"))
      (node (ref "J6") (pin "4") (pinfunction "4_4") (pintype "passive"))
      (node (ref "R28") (pin "1") (pinfunction "1_1") (pintype "passive"))
      (node (ref "U2") (pin "6") (pinfunction "-IN_6") (pintype "input"))
    )
    (net (code "26") (name "THER6-SIG") (class "Default")
      (node (ref "J11") (pin "8") (pinfunction "8_8") (pintype "bidirectional"))
      (node (ref "R31") (pin "1") (pinfunction "1_1") (pintype "passive"))
      (node (ref "R34") (pin "1") (pinfunction "1_1") (pintype "passive"))
      (node (ref "U2") (pin "1") (pinfunction "OUT_1") (pintype "output"))
    )
    (net (code "27") (name "THER7-IN") (class "Default")
      (node (ref "CR7") (pin "3") (pinfunction "3_3") (pintype "passive"))
      (node (ref "J7") (pin "4") (pinfunction "4_4") (pintype "passive"))
      (node (ref "R29") (pin "1") (pinfunction "1_1") (pintype "passive"))
      (node (ref "U2") (pin "4") (pinfunction "-IN_4") (pintype "input"))
    )
    (net (code "28") (name "THER7-SIG") (class "Default")
      (node (ref "J11") (pin "9") (pinfunction "9_9") (pintype "bidirectional"))
      (node (ref "R32") (pin "1") (pinfunction "1_1") (pintype "passive"))
      (node (ref "R35") (pin "1") (pinfunction "1_1") (pintype "passive"))
      (node (ref "U2") (pin "2") (pinfunction "OUT_2") (pintype "output"))
    )
    (net (code "29") (name "THER8-IN") (class "Default")
      (node (ref "CR8") (pin "3") (pinfunction "3_3") (pintype "passive"))
      (node (ref "J8") (pin "4") (pinfunction "4_4") (pintype "passive"))
      (node (ref "R42") (pin "1") (pinfunction "1_1") (pintype "passive"))
      (node (ref "U3") (pin "8") (pinfunction "-IN_8") (pintype "input"))
    )
    (net (code "30") (name "THER8-SIG") (class "Default")
      (node (ref "J11") (pin "7") (pinfunction "7_7") (pintype "bidirectional"))
      (node (ref "R45") (pin "1") (pinfunction "1_1") (pintype "passive"))
      (node (ref "R48") (pin "1") (pinfunction "1_1") (pintype "passive"))
      (node (ref "U3") (pin "14") (pinfunction "OUT_14") (pintype "output"))
    )
    (net (code "31") (name "THER9-IN") (class "Default")
      (node (ref "CR9") (pin "3") (pinfunction "3_3") (pintype "passive"))
      (node (ref "J9") (pin "4") (pinfunction "4_4") (pintype "passive"))
      (node (ref "R43") (pin "1") (pinfunction "1_1") (pintype "passive"))
      (node (ref "U3") (pin "6") (pinfunction "-IN_6") (pintype "input"))
    )
    (net (code "32") (name "THER9-SIG") (class "Default")
      (node (ref "J11") (pin "6") (pinfunction "6_6") (pintype "bidirectional"))
      (node (ref "R46") (pin "1") (pinfunction "1_1") (pintype "passive"))
      (node (ref "R49") (pin "1") (pinfunction "1_1") (pintype "passive"))
      (node (ref "U3") (pin "1") (pinfunction "OUT_1") (pintype "output"))
    )
    (net (code "33") (name "THER10-IN") (class "Default")
      (node (ref "CR10") (pin "3") (pinfunction "3_3") (pintype "passive"))
      (node (ref "J10") (pin "4") (pinfunction "4_4") (pintype "passive"))
      (node (ref "R44") (pin "1") (pinfunction "1_1") (pintype "passive"))
      (node (ref "U3") (pin "4") (pinfunction "-IN_4") (pintype "input"))
    )
    (net (code "34") (name "THER10-SIG") (class "Default")
      (node (ref "J11") (pin "5") (pinfunction "5_5") (pintype "bidirectional"))
      (node (ref "R47") (pin "1") (pinfunction "1_1") (pintype "passive"))
      (node (ref "R50") (pin "1") (pinfunction "1_1") (pintype "passive"))
      (node (ref "U3") (pin "2") (pinfunction "OUT_2") (pintype "output"))
    )
    (net (code "35") (name "unconnected-(CR1-NC-Pad2)") (class "Default")
      (node (ref "CR1") (pin "2") (pinfunction "NC_2") (pintype "no_connect"))
    )
    (net (code "36") (name "unconnected-(CR2-NC-Pad2)") (class "Default")
      (node (ref "CR2") (pin "2") (pinfunction "NC_2") (pintype "no_connect"))
    )
    (net (code "37") (name "unconnected-(CR3-NC-Pad2)") (class "Default")
      (node (ref "CR3") (pin "2") (pinfunction "NC_2") (pintype "no_connect"))
    )
    (net (code "38") (name "unconnected-(CR4-NC-Pad2)") (class "Default")
      (node (ref "CR4") (pin "2") (pinfunction "NC_2") (pintype "no_connect"))
    )
    (net (code "39") (name "unconnected-(CR5-NC-Pad2)") (class "Default")
      (node (ref "CR5") (pin "2") (pinfunction "NC_2") (pintype "no_connect"))
    )
    (net (code "40") (name "unconnected-(CR6-NC-Pad2)") (class "Default")
      (node (ref "CR6") (pin "2") (pinfunction "NC_2") (pintype "no_connect"))
    )
    (net (code "41") (name "unconnected-(CR7-NC-Pad2)") (class "Default")
      (node (ref "CR7") (pin "2") (pinfunction "NC_2") (pintype "no_connect"))
    )
    (net (code "42") (name "unconnected-(CR8-NC-Pad2)") (class "Default")
      (node (ref "CR8") (pin "2") (pinfunction "NC_2") (pintype "no_connect"))
    )
    (net (code "43") (name "unconnected-(CR9-NC-Pad2)") (class "Default")
      (node (ref "CR9") (pin "2") (pinfunction "NC_2") (pintype "no_connect"))
    )
    (net (code "44") (name "unconnected-(CR10-NC-Pad2)") (class "Default")
      (node (ref "CR10") (pin "2") (pinfunction "NC_2") (pintype "no_connect"))
    )
    (net (code "45") (name "unconnected-(J1-SHIELD-PadS1)") (class "Default")
      (node (ref "J1") (pin "S1") (pinfunction "SHIELD_S1") (pintype "passive"))
    )
    (net (code "46") (name "unconnected-(J2-SHIELD-PadS1)") (class "Default")
      (node (ref "J2") (pin "S1") (pinfunction "SHIELD_S1") (pintype "passive"))
    )
    (net (code "47") (name "unconnected-(J3-SHIELD-PadS1)") (class "Default")
      (node (ref "J3") (pin "S1") (pinfunction "SHIELD_S1") (pintype "passive"))
    )
    (net (code "48") (name "unconnected-(J4-SHIELD-PadS1)") (class "Default")
      (node (ref "J4") (pin "S1") (pinfunction "SHIELD_S1") (pintype "passive"))
    )
    (net (code "49") (name "unconnected-(J5-SHIELD-PadS1)") (class "Default")
      (node (ref "J5") (pin "S1") (pinfunction "SHIELD_S1") (pintype "passive"))
    )
    (net (code "50") (name "unconnected-(J6-SHIELD-PadS1)") (class "Default")
      (node (ref "J6") (pin "S1") (pinfunction "SHIELD_S1") (pintype "passive"))
    )
    (net (code "51") (name "unconnected-(J7-SHIELD-PadS1)") (class "Default")
      (node (ref "J7") (pin "S1") (pinfunction "SHIELD_S1") (pintype "passive"))
    )
    (net (code "52") (name "unconnected-(J8-SHIELD-PadS1)") (class "Default")
      (node (ref "J8") (pin "S1") (pinfunction "SHIELD_S1") (pintype "passive"))
    )
    (net (code "53") (name "unconnected-(J9-SHIELD-PadS1)") (class "Default")
      (node (ref "J9") (pin "S1") (pinfunction "SHIELD_S1") (pintype "passive"))
    )
    (net (code "54") (name "unconnected-(J10-SHIELD-PadS1)") (class "Default")
      (node (ref "J10") (pin "S1") (pinfunction "SHIELD_S1") (pintype "passive"))
    )
    (net (code "55") (name "unconnected-(J11-Pad16)") (class "Default")
      (node (ref "J11") (pin "16") (pinfunction "16_16") (pintype "bidirectional"))
    )
  )
)
